# logi-cmos-7725-7670-NoFFC.net
KiCad netlist of a schematic drawn in Altium Designer
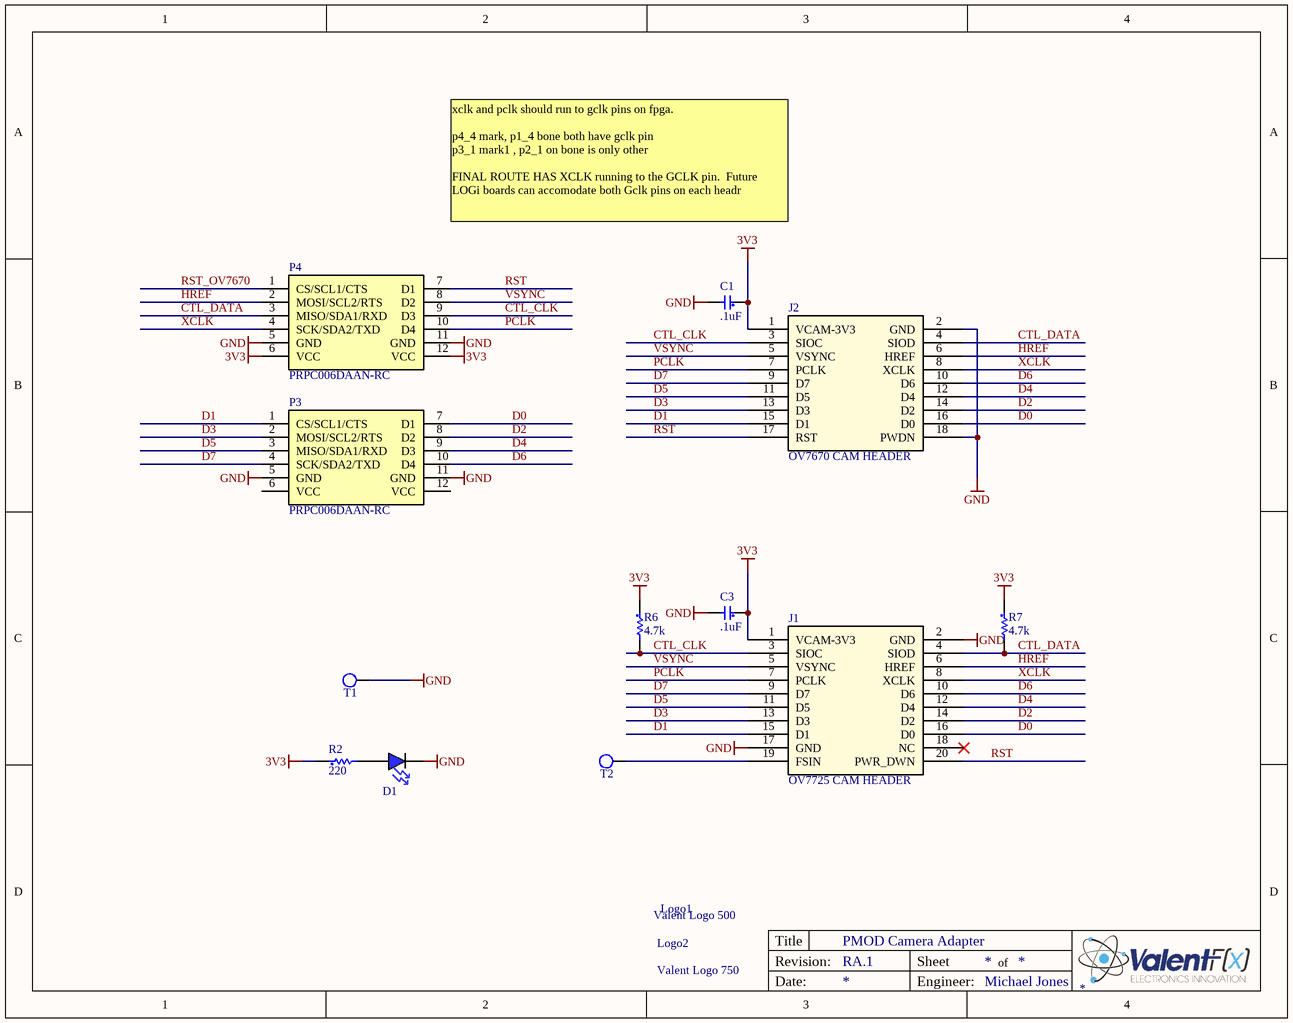
[diagram p0: logi-cmos-7725-7670-NoFFC.SchDoc]

(export (version "E")
  (design (tool "Eeschema 10.0.6"))
  (components
    (comp (ref "C1")
      (value ".1uF")
      (footprint "mRCL:C0603")
      (description ".10uF X7R 20% (MLCC) - SMD/SMT 0603 25volts")
      (fields (field (name "MANUFACTURER") "TDK") (field (name "MANUFACTURER PART NUMBER") "C1608X7R1E104MT"))
      (libsource (lib "mCapacitors") (part "C0603 - C1608X7R1E104MT"))
    )
    (comp (ref "C3")
      (value ".1uF")
      (footprint "mRCL:C0603")
      (description ".10uF X7R 20% (MLCC) - SMD/SMT 0603 25volts")
      (fields (field (name "MANUFACTURER") "TDK") (field (name "MANUFACTURER PART NUMBER") "C1608X7R1E104MT"))
      (libsource (lib "mCapacitors") (part "C0603 - C1608X7R1E104MT"))
    )
    (comp (ref "D1")
      (value "BLUE LED0603")
      (footprint "LED_0603 - BLUE")
      (description "BLUE Standard LED - SMD Blue 470nm 40mcd 20mA")
      (fields
        (field (name "MANUFACTURER") "Harvatek International")
        (field (name "MANUFACTURER PART NUMBER") "HT-193NB-5589")
      )
      (libsource (lib "mDiode") (part "LED0603 - HT-193NB-5589"))
    )
    (comp (ref "J1")
      (value "OV7725 CAM HEADER")
      (footprint "HEADER_10x2_40_100 1-3-5 THRU DIP")
      (description "CMOS CAMERA HEADER")
      (fields
        (field (name "MANUFACTURER") "Sullins Connector Solutions")
        (field (name "MANUFACTURER PART NUMBER") "SFH11-PBPC-D10-ST-BK")
      )
      (libsource (lib "mModule") (part "CAM - 0V7725"))
    )
    (comp (ref "J2")
      (value "OV7670 CAM HEADER")
      (footprint "HEADER_9x2_40_100 1-3-5 THRU DIP")
      (description "CMOS CAMERA HEADER")
      (fields
        (field (name "MANUFACTURER") "Sullins Connector Solutions")
        (field (name "MANUFACTURER PART NUMBER") "PPPC092LFBN-RC")
      )
      (libsource (lib "mModule") (part "CAM - OV7670"))
    )
    (comp (ref "Logo1")
      (value "Valent Logo 500")
      (footprint "VALENTFX_500-SolderMask")
      (libsource (lib "mLogos") (part "Valent Logo 500"))
    )
    (comp (ref "Logo2")
      (value "Valent Logo 750")
      (footprint "VALENTFX_750-SolderMask-BOT")
      (libsource (lib "mLogos") (part "Valent Logo 750"))
    )
    (comp (ref "P3")
      (value "PRPC006DAAN-RC")
      (footprint "mconnector:PMOD HEADER - Male")
      (fields
        (field (name "MANUFACTURER") "Samtec")
        (field (name "MANUFACTURER PART NUMBER") "MTSW-106-07-G-D-130-RA")
      )
      (libsource (lib "mConnector") (part "PRPC006DAAN-RC"))
    )
    (comp (ref "P4")
      (value "PRPC006DAAN-RC")
      (footprint "mconnector:PMOD HEADER - Male")
      (fields
        (field (name "MANUFACTURER") "Samtec")
        (field (name "MANUFACTURER PART NUMBER") "MTSW-106-07-G-D-130-RA")
      )
      (libsource (lib "mConnector") (part "PRPC006DAAN-RC"))
    )
    (comp (ref "R2")
      (value "220")
      (footprint "mRCL:R0603")
      (description "220 - thick Film Resistors - SMD 0603 220ohms 1% Tol")
      (fields
        (field (name "MANUFACTURER") "Panasonic - ECG")
        (field (name "MANUFACTURER PART NUMBER") "ERJ-3EKF2200V")
      )
      (libsource (lib "mResistors") (part "R0603 - ERJ-3EKF2200V"))
    )
    (comp (ref "R6")
      (value "4.7k")
      (footprint "mRCL:R0603")
      (description "4.7k Thick Film Resistors - SMD 1/10watt 4.7Kohms 1%")
      (fields
        (field (name "MANUFACTURER") "Vishay Dale")
        (field (name "MANUFACTURER PART NUMBER") "CRCW06034K70FKEA")
      )
      (libsource (lib "mResistors") (part "R0603 - CRCW06034K70FKEA"))
    )
    (comp (ref "R7")
      (value "4.7k")
      (footprint "mRCL:R0603")
      (description "4.7k Thick Film Resistors - SMD 1/10watt 4.7Kohms 1%")
      (fields
        (field (name "MANUFACTURER") "Vishay Dale")
        (field (name "MANUFACTURER PART NUMBER") "CRCW06034K70FKEA")
      )
      (libsource (lib "mResistors") (part "R0603 - CRCW06034K70FKEA"))
    )
    (comp (ref "T1")
      (value "Test Point")
      (footprint "Tp 25-40")
      (description "Test Point Smaller Symbol")
      (libsource (lib "mConnector") (part "Test Point 2"))
    )
    (comp (ref "T2")
      (value "Test Point")
      (footprint "Tp 25-40")
      (description "Test Point Smaller Symbol")
      (libsource (lib "mConnector") (part "Test Point 2"))
    )
  )
  (nets
    (net (code "1") (name "/CTL_CLK") (class "Default")
      (node (ref "J1") (pin "3") (pinfunction "SIOC_3") (pintype "passive"))
      (node (ref "J2") (pin "3") (pinfunction "SIOC_3") (pintype "passive"))
      (node (ref "P4") (pin "9") (pinfunction "D3_9") (pintype "power_in"))
      (node (ref "R6") (pin "2") (pinfunction "2_2") (pintype "passive"))
    )
    (net (code "2") (name "/CTL_DATA") (class "Default")
      (node (ref "J1") (pin "4") (pinfunction "SIOD_4") (pintype "passive"))
      (node (ref "J2") (pin "4") (pinfunction "SIOD_4") (pintype "passive"))
      (node (ref "P4") (pin "3") (pinfunction "MISO/SDA1/RXD_3") (pintype "power_in"))
      (node (ref "R7") (pin "2") (pinfunction "2_2") (pintype "passive"))
    )
    (net (code "3") (name "/D0") (class "Default")
      (node (ref "J1") (pin "16") (pinfunction "D0_16") (pintype "passive"))
      (node (ref "J2") (pin "16") (pinfunction "D0_16") (pintype "passive"))
      (node (ref "P3") (pin "7") (pinfunction "D1_7") (pintype "power_in"))
    )
    (net (code "4") (name "/D1") (class "Default")
      (node (ref "J1") (pin "15") (pinfunction "D1_15") (pintype "passive"))
      (node (ref "J2") (pin "15") (pinfunction "D1_15") (pintype "passive"))
      (node (ref "P3") (pin "1") (pinfunction "CS/SCL1/CTS_1") (pintype "power_in"))
    )
    (net (code "5") (name "/D2") (class "Default")
      (node (ref "J1") (pin "14") (pinfunction "D2_14") (pintype "passive"))
      (node (ref "J2") (pin "14") (pinfunction "D2_14") (pintype "passive"))
      (node (ref "P3") (pin "8") (pinfunction "D2_8") (pintype "power_in"))
    )
    (net (code "6") (name "/D3") (class "Default")
      (node (ref "J1") (pin "13") (pinfunction "D3_13") (pintype "passive"))
      (node (ref "J2") (pin "13") (pinfunction "D3_13") (pintype "passive"))
      (node (ref "P3") (pin "2") (pinfunction "MOSI/SCL2/RTS_2") (pintype "power_in"))
    )
    (net (code "7") (name "/D4") (class "Default")
      (node (ref "J1") (pin "12") (pinfunction "D4_12") (pintype "passive"))
      (node (ref "J2") (pin "12") (pinfunction "D4_12") (pintype "passive"))
      (node (ref "P3") (pin "9") (pinfunction "D3_9") (pintype "power_in"))
    )
    (net (code "8") (name "/D5") (class "Default")
      (node (ref "J1") (pin "11") (pinfunction "D5_11") (pintype "passive"))
      (node (ref "J2") (pin "11") (pinfunction "D5_11") (pintype "passive"))
      (node (ref "P3") (pin "3") (pinfunction "MISO/SDA1/RXD_3") (pintype "power_in"))
    )
    (net (code "9") (name "/D6") (class "Default")
      (node (ref "J1") (pin "10") (pinfunction "D6_10") (pintype "passive"))
      (node (ref "J2") (pin "10") (pinfunction "D6_10") (pintype "passive"))
      (node (ref "P3") (pin "10") (pinfunction "D4_10") (pintype "power_in"))
    )
    (net (code "10") (name "/D7") (class "Default")
      (node (ref "J1") (pin "9") (pinfunction "D7_9") (pintype "passive"))
      (node (ref "J2") (pin "9") (pinfunction "D7_9") (pintype "passive"))
      (node (ref "P3") (pin "4") (pinfunction "SCK/SDA2/TXD_4") (pintype "power_in"))
    )
    (net (code "11") (name "/HREF") (class "Default")
      (node (ref "J1") (pin "6") (pinfunction "HREF_6") (pintype "passive"))
      (node (ref "J2") (pin "6") (pinfunction "HREF_6") (pintype "passive"))
      (node (ref "P4") (pin "2") (pinfunction "MOSI/SCL2/RTS_2") (pintype "power_in"))
    )
    (net (code "12") (name "/PCLK") (class "Default")
      (node (ref "J1") (pin "7") (pinfunction "PCLK_7") (pintype "passive"))
      (node (ref "J2") (pin "7") (pinfunction "PCLK_7") (pintype "passive"))
      (node (ref "P4") (pin "10") (pinfunction "D4_10") (pintype "power_in"))
    )
    (net (code "13") (name "/RST") (class "Default")
      (node (ref "J1") (pin "20") (pinfunction "PWR_DWN_20") (pintype "passive"))
      (node (ref "J2") (pin "17") (pinfunction "RST_17") (pintype "passive"))
      (node (ref "P4") (pin "7") (pinfunction "D1_7") (pintype "power_in"))
    )
    (net (code "14") (name "/RST_OV7670") (class "Default")
      (node (ref "P4") (pin "1") (pinfunction "CS/SCL1/CTS_1") (pintype "power_in"))
    )
    (net (code "15") (name "/VSYNC") (class "Default")
      (node (ref "J1") (pin "5") (pinfunction "VSYNC_5") (pintype "passive"))
      (node (ref "J2") (pin "5") (pinfunction "VSYNC_5") (pintype "passive"))
      (node (ref "P4") (pin "8") (pinfunction "D2_8") (pintype "power_in"))
    )
    (net (code "16") (name "/XCLK") (class "Default")
      (node (ref "J1") (pin "8") (pinfunction "XCLK_8") (pintype "passive"))
      (node (ref "J2") (pin "8") (pinfunction "XCLK_8") (pintype "passive"))
      (node (ref "P4") (pin "4") (pinfunction "SCK/SDA2/TXD_4") (pintype "power_in"))
    )
    (net (code "17") (name "3V3") (class "Default")
      (node (ref "C1") (pin "1") (pinfunction "1_1") (pintype "passive"))
      (node (ref "C3") (pin "1") (pinfunction "1_1") (pintype "passive"))
      (node (ref "J1") (pin "1") (pinfunction "VCAM-3V3_1") (pintype "passive"))
      (node (ref "J2") (pin "1") (pinfunction "VCAM-3V3_1") (pintype "passive"))
      (node (ref "P4") (pin "12") (pinfunction "VCC_12") (pintype "power_in"))
      (node (ref "P4") (pin "6") (pinfunction "VCC_6") (pintype "power_in"))
      (node (ref "R2") (pin "1") (pinfunction "1_1") (pintype "passive"))
      (node (ref "R6") (pin "1") (pinfunction "1_1") (pintype "passive"))
      (node (ref "R7") (pin "1") (pinfunction "1_1") (pintype "passive"))
    )
    (net (code "18") (name "GND") (class "Default")
      (node (ref "C1") (pin "2") (pinfunction "2_2") (pintype "passive"))
      (node (ref "C3") (pin "2") (pinfunction "2_2") (pintype "passive"))
      (node (ref "D1") (pin "C") (pinfunction "C_C") (pintype "passive"))
      (node (ref "J1") (pin "17") (pinfunction "GND_17") (pintype "passive"))
      (node (ref "J1") (pin "2") (pinfunction "GND_2") (pintype "passive"))
      (node (ref "J2") (pin "18") (pinfunction "PWDN_18") (pintype "passive"))
      (node (ref "J2") (pin "2") (pinfunction "GND_2") (pintype "passive"))
      (node (ref "P3") (pin "11") (pinfunction "GND_11") (pintype "power_in"))
      (node (ref "P3") (pin "5") (pinfunction "GND_5") (pintype "power_in"))
      (node (ref "P4") (pin "11") (pinfunction "GND_11") (pintype "power_in"))
      (node (ref "P4") (pin "5") (pinfunction "GND_5") (pintype "power_in"))
      (node (ref "T1") (pin "1") (pinfunction "1_1") (pintype "passive"))
    )
    (net (code "19") (name "Net-(D1-PadA)") (class "Default")
      (node (ref "D1") (pin "A") (pinfunction "A_A") (pintype "passive"))
      (node (ref "R2") (pin "2") (pinfunction "2_2") (pintype "passive"))
    )
    (net (code "20") (name "Net-(J1-FSIN)") (class "Default")
      (node (ref "J1") (pin "19") (pinfunction "FSIN_19") (pintype "passive"))
      (node (ref "T2") (pin "1") (pinfunction "1_1") (pintype "passive"))
    )
    (net (code "21") (name "unconnected-(J1-NC-Pad18)") (class "Default")
      (node (ref "J1") (pin "18") (pinfunction "NC_18") (pintype "passive+no_connect"))
    )
    (net (code "22") (name "unconnected-(P3-VCC-Pad6)") (class "Default")
      (node (ref "P3") (pin "6") (pinfunction "VCC_6") (pintype "power_in"))
    )
    (net (code "23") (name "unconnected-(P3-VCC-Pad12)") (class "Default")
      (node (ref "P3") (pin "12") (pinfunction "VCC_12") (pintype "power_in"))
    )
  )
)
